# Arduino_CAN_shield_sch_V1_0.net
KiCad netlist of a schematic drawn in Altium Designer
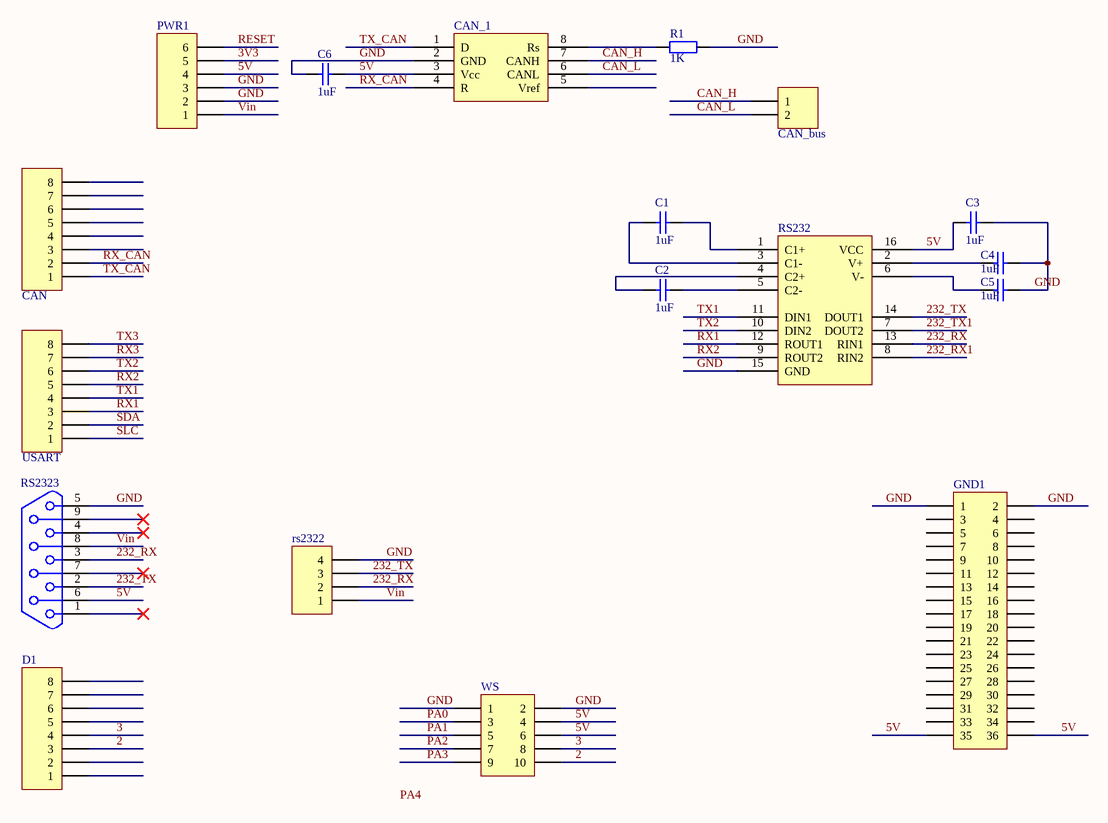
[diagram p0: Arduino CAN shield sch_V1.0.SchDoc]

(export (version "E")
  (design (tool "Eeschema 10.0.6"))
  (components
    (comp (ref "C1")
      (value "1uF")
      (footprint "0805C")
      (description "Capacitor")
      (fields (field (name "PUBLISHER") "Altium Limited"))
      (libsource (lib "Schlib1") (part "Cap"))
    )
    (comp (ref "C2")
      (value "1uF")
      (footprint "0805C")
      (description "Capacitor")
      (fields (field (name "PUBLISHER") "Altium Limited"))
      (libsource (lib "Schlib1") (part "Cap"))
    )
    (comp (ref "C3")
      (value "1uF")
      (footprint "0805C")
      (description "Capacitor")
      (fields (field (name "PUBLISHER") "Altium Limited"))
      (libsource (lib "Schlib1") (part "Cap"))
    )
    (comp (ref "C4")
      (value "1uF")
      (footprint "0805C")
      (description "Capacitor")
      (fields (field (name "PUBLISHER") "Altium Limited"))
      (libsource (lib "Schlib1") (part "Cap"))
    )
    (comp (ref "C5")
      (value "1uF")
      (footprint "0805C")
      (description "Capacitor")
      (fields (field (name "PUBLISHER") "Altium Limited"))
      (libsource (lib "Schlib1") (part "Cap"))
    )
    (comp (ref "C6")
      (value "1uF")
      (footprint "0805C")
      (description "Capacitor")
      (fields (field (name "PUBLISHER") "Altium Limited"))
      (libsource (lib "Schlib1") (part "Cap"))
    )
    (comp (ref "CAN") (value "Header 8") (footprint "HDR1X8") (libsource (lib "Schlib1") (part "Header 8")))
    (comp (ref "CAN_1") (value "VP230") (footprint "SI4435") (libsource (lib "Schlib1") (part "VP230")))
    (comp (ref "CAN_bus")
      (value "Header 2_3")
      (footprint "HDR1X2-can")
      (description "Header, 2-Pin")
      (fields (field (name "PUBLISHER") "Altium Limited"))
      (libsource (lib "Schlib1") (part "Header 2_3"))
    )
    (comp (ref "D1") (value "Header 8") (footprint "HDR1X8") (libsource (lib "Schlib1") (part "Header 8")))
    (comp (ref "GND1")
      (value "Header 18X2H")
      (footprint "HDR2X18")
      (description "Header, 18-Pin, Dual row, Right Angle")
      (fields (field (name "PUBLISHER") "Altium Limited"))
      (libsource (lib "Schlib1") (part "Header 18X2H"))
    )
    (comp (ref "PWR1")
      (value "Header 6_1")
      (footprint "HDR1X6")
      (description "Header, 6-Pin")
      (fields (field (name "PUBLISHER") "Altium Limited"))
      (libsource (lib "Schlib1") (part "Header 6_1"))
    )
    (comp (ref "R1")
      (value "1K")
      (footprint "0805R")
      (description "Resistor")
      (fields (field (name "PUBLISHER") "Altium Limited"))
      (libsource (lib "Schlib1") (part "Res2"))
    )
    (comp (ref "RS232") (value "MAX232D") (footprint "TSSOP-16") (libsource (lib "Schlib1") (part "MAX232D")))
    (comp (ref "rs2322")
      (value "Header 4_1")
      (footprint "HDR1X4")
      (description "Header, 4-Pin")
      (fields (field (name "PUBLISHER") "Altium Limited"))
      (libsource (lib "Schlib1") (part "Header 4_1"))
    )
    (comp (ref "RS2323") (value "DB9") (footprint "DB9RA/F") (libsource (lib "Schlib1") (part "DB9")))
    (comp (ref "USART") (value "Header 8") (footprint "HDR1X8") (libsource (lib "Schlib1") (part "Header 8")))
    (comp (ref "WS")
      (value "Header 5X2_3")
      (footprint "HDR2X5")
      (description "Header, 5-Pin, Dual row")
      (fields (field (name "PUBLISHER") "Altium Limited"))
      (libsource (lib "Schlib1") (part "Header 5X2_3"))
    )
  )
  (nets
    (net (code "1") (name "/2") (class "Default")
      (node (ref "D1") (pin "3") (pinfunction "3_3") (pintype "passive"))
      (node (ref "WS") (pin "10") (pinfunction "10_10") (pintype "passive"))
    )
    (net (code "2") (name "/3") (class "Default")
      (node (ref "D1") (pin "4") (pinfunction "4_4") (pintype "passive"))
      (node (ref "WS") (pin "8") (pinfunction "8_8") (pintype "passive"))
    )
    (net (code "3") (name "/3V3") (class "Default")
      (node (ref "PWR1") (pin "5") (pinfunction "5_5") (pintype "passive"))
    )
    (net (code "4") (name "/5V") (class "Default")
      (node (ref "C3") (pin "1") (pinfunction "1_1") (pintype "passive"))
      (node (ref "C6") (pin "1") (pinfunction "1_1") (pintype "passive"))
      (node (ref "CAN_1") (pin "3") (pinfunction "Vcc_3") (pintype "passive"))
      (node (ref "GND1") (pin "35") (pinfunction "35_35") (pintype "passive"))
      (node (ref "GND1") (pin "36") (pinfunction "36_36") (pintype "passive"))
      (node (ref "PWR1") (pin "4") (pinfunction "4_4") (pintype "passive"))
      (node (ref "RS232") (pin "16") (pinfunction "VCC_16") (pintype "passive"))
      (node (ref "RS2323") (pin "6") (pinfunction "6_6") (pintype "passive"))
      (node (ref "WS") (pin "4") (pinfunction "4_4") (pintype "passive"))
      (node (ref "WS") (pin "6") (pinfunction "6_6") (pintype "passive"))
    )
    (net (code "5") (name "/232_RX") (class "Default")
      (node (ref "RS232") (pin "13") (pinfunction "RIN1_13") (pintype "passive"))
      (node (ref "RS2323") (pin "3") (pinfunction "3_3") (pintype "passive"))
      (node (ref "rs2322") (pin "2") (pinfunction "2_2") (pintype "passive"))
    )
    (net (code "6") (name "/232_RX1") (class "Default")
      (node (ref "RS232") (pin "8") (pinfunction "RIN2_8") (pintype "passive"))
    )
    (net (code "7") (name "/232_TX") (class "Default")
      (node (ref "RS232") (pin "14") (pinfunction "DOUT1_14") (pintype "passive"))
      (node (ref "RS2323") (pin "2") (pinfunction "2_2") (pintype "passive"))
      (node (ref "rs2322") (pin "3") (pinfunction "3_3") (pintype "passive"))
    )
    (net (code "8") (name "/232_TX1") (class "Default")
      (node (ref "RS232") (pin "7") (pinfunction "DOUT2_7") (pintype "passive"))
    )
    (net (code "9") (name "/CAN_H") (class "Default")
      (node (ref "CAN_1") (pin "7") (pinfunction "CANH_7") (pintype "passive"))
      (node (ref "CAN_bus") (pin "1") (pinfunction "1_1") (pintype "passive"))
    )
    (net (code "10") (name "/CAN_L") (class "Default")
      (node (ref "CAN_1") (pin "6") (pinfunction "CANL_6") (pintype "passive"))
      (node (ref "CAN_bus") (pin "2") (pinfunction "2_2") (pintype "passive"))
    )
    (net (code "11") (name "/GND") (class "Default")
      (node (ref "C3") (pin "2") (pinfunction "2_2") (pintype "passive"))
      (node (ref "C4") (pin "1") (pinfunction "1_1") (pintype "passive"))
      (node (ref "C5") (pin "1") (pinfunction "1_1") (pintype "passive"))
      (node (ref "C6") (pin "2") (pinfunction "2_2") (pintype "passive"))
      (node (ref "CAN_1") (pin "2") (pinfunction "GND_2") (pintype "passive"))
      (node (ref "GND1") (pin "1") (pinfunction "1_1") (pintype "passive"))
      (node (ref "GND1") (pin "2") (pinfunction "2_2") (pintype "passive"))
      (node (ref "PWR1") (pin "2") (pinfunction "2_2") (pintype "passive"))
      (node (ref "PWR1") (pin "3") (pinfunction "3_3") (pintype "passive"))
      (node (ref "R1") (pin "2") (pinfunction "2_2") (pintype "passive"))
      (node (ref "RS232") (pin "15") (pinfunction "GND_15") (pintype "passive"))
      (node (ref "RS2323") (pin "5") (pinfunction "5_5") (pintype "passive"))
      (node (ref "WS") (pin "1") (pinfunction "1_1") (pintype "passive"))
      (node (ref "WS") (pin "2") (pinfunction "2_2") (pintype "passive"))
      (node (ref "rs2322") (pin "4") (pinfunction "4_4") (pintype "passive"))
    )
    (net (code "12") (name "/PA0") (class "Default")
      (node (ref "WS") (pin "3") (pinfunction "3_3") (pintype "passive"))
    )
    (net (code "13") (name "/PA1") (class "Default")
      (node (ref "WS") (pin "5") (pinfunction "5_5") (pintype "passive"))
    )
    (net (code "14") (name "/PA2") (class "Default")
      (node (ref "WS") (pin "7") (pinfunction "7_7") (pintype "passive"))
    )
    (net (code "15") (name "/PA3") (class "Default")
      (node (ref "WS") (pin "9") (pinfunction "9_9") (pintype "passive"))
    )
    (net (code "17") (name "/RESET") (class "Default")
      (node (ref "PWR1") (pin "6") (pinfunction "6_6") (pintype "passive"))
    )
    (net (code "18") (name "/RX1") (class "Default")
      (node (ref "RS232") (pin "12") (pinfunction "ROUT1_12") (pintype "passive"))
      (node (ref "USART") (pin "3") (pinfunction "3_3") (pintype "passive"))
    )
    (net (code "19") (name "/RX2") (class "Default")
      (node (ref "RS232") (pin "9") (pinfunction "ROUT2_9") (pintype "passive"))
      (node (ref "USART") (pin "5") (pinfunction "5_5") (pintype "passive"))
    )
    (net (code "20") (name "/RX3") (class "Default")
      (node (ref "USART") (pin "7") (pinfunction "7_7") (pintype "passive"))
    )
    (net (code "21") (name "/RX_CAN") (class "Default")
      (node (ref "CAN") (pin "2") (pinfunction "2_2") (pintype "passive"))
      (node (ref "CAN_1") (pin "4") (pinfunction "R_4") (pintype "passive"))
    )
    (net (code "22") (name "/SDA") (class "Default")
      (node (ref "USART") (pin "2") (pinfunction "2_2") (pintype "passive"))
    )
    (net (code "23") (name "/SLC") (class "Default")
      (node (ref "USART") (pin "1") (pinfunction "1_1") (pintype "passive"))
    )
    (net (code "24") (name "/TX1") (class "Default")
      (node (ref "RS232") (pin "11") (pinfunction "DIN1_11") (pintype "passive"))
      (node (ref "USART") (pin "4") (pinfunction "4_4") (pintype "passive"))
    )
    (net (code "25") (name "/TX2") (class "Default")
      (node (ref "RS232") (pin "10") (pinfunction "DIN2_10") (pintype "passive"))
      (node (ref "USART") (pin "6") (pinfunction "6_6") (pintype "passive"))
    )
    (net (code "26") (name "/TX3") (class "Default")
      (node (ref "USART") (pin "8") (pinfunction "8_8") (pintype "passive"))
    )
    (net (code "27") (name "/TX_CAN") (class "Default")
      (node (ref "CAN") (pin "1") (pinfunction "1_1") (pintype "passive"))
      (node (ref "CAN_1") (pin "1") (pinfunction "D_1") (pintype "passive"))
    )
    (net (code "28") (name "/Vin") (class "Default")
      (node (ref "PWR1") (pin "1") (pinfunction "1_1") (pintype "passive"))
      (node (ref "RS2323") (pin "8") (pinfunction "8_8") (pintype "passive"))
      (node (ref "rs2322") (pin "1") (pinfunction "1_1") (pintype "passive"))
    )
    (net (code "29") (name "Net-(CAN_1-Rs)") (class "Default")
      (node (ref "CAN_1") (pin "8") (pinfunction "Rs_8") (pintype "passive"))
      (node (ref "R1") (pin "1") (pinfunction "1_1") (pintype "passive"))
    )
    (net (code "30") (name "Net-(RS232-C1+)") (class "Default")
      (node (ref "C1") (pin "1") (pinfunction "1_1") (pintype "passive"))
      (node (ref "RS232") (pin "1") (pinfunction "C1+_1") (pintype "passive"))
    )
    (net (code "31") (name "Net-(RS232-C1-)") (class "Default")
      (node (ref "C1") (pin "2") (pinfunction "2_2") (pintype "passive"))
      (node (ref "RS232") (pin "3") (pinfunction "C1-_3") (pintype "passive"))
    )
    (net (code "32") (name "Net-(RS232-C2+)") (class "Default")
      (node (ref "C2") (pin "2") (pinfunction "2_2") (pintype "passive"))
      (node (ref "RS232") (pin "4") (pinfunction "C2+_4") (pintype "passive"))
    )
    (net (code "33") (name "Net-(RS232-C2-)") (class "Default")
      (node (ref "C2") (pin "1") (pinfunction "1_1") (pintype "passive"))
      (node (ref "RS232") (pin "5") (pinfunction "C2-_5") (pintype "passive"))
    )
    (net (code "34") (name "Net-(RS232-V+)") (class "Default")
      (node (ref "C4") (pin "2") (pinfunction "2_2") (pintype "passive"))
      (node (ref "RS232") (pin "2") (pinfunction "V+_2") (pintype "passive"))
    )
    (net (code "35") (name "Net-(RS232-V-)") (class "Default")
      (node (ref "C5") (pin "2") (pinfunction "2_2") (pintype "passive"))
      (node (ref "RS232") (pin "6") (pinfunction "V-_6") (pintype "passive"))
    )
    (net (code "36") (name "unconnected-(CAN-Pad3)") (class "Default")
      (node (ref "CAN") (pin "3") (pinfunction "3_3") (pintype "passive"))
    )
    (net (code "37") (name "unconnected-(CAN-Pad4)") (class "Default")
      (node (ref "CAN") (pin "4") (pinfunction "4_4") (pintype "passive"))
    )
    (net (code "38") (name "unconnected-(CAN-Pad5)") (class "Default")
      (node (ref "CAN") (pin "5") (pinfunction "5_5") (pintype "passive"))
    )
    (net (code "39") (name "unconnected-(CAN-Pad6)") (class "Default")
      (node (ref "CAN") (pin "6") (pinfunction "6_6") (pintype "passive"))
    )
    (net (code "40") (name "unconnected-(CAN-Pad7)") (class "Default")
      (node (ref "CAN") (pin "7") (pinfunction "7_7") (pintype "passive"))
    )
    (net (code "41") (name "unconnected-(CAN-Pad8)") (class "Default")
      (node (ref "CAN") (pin "8") (pinfunction "8_8") (pintype "passive"))
    )
    (net (code "42") (name "unconnected-(CAN_1-Vref-Pad5)") (class "Default")
      (node (ref "CAN_1") (pin "5") (pinfunction "Vref_5") (pintype "passive"))
    )
    (net (code "43") (name "unconnected-(D1-Pad1)") (class "Default")
      (node (ref "D1") (pin "1") (pinfunction "1_1") (pintype "passive"))
    )
    (net (code "44") (name "unconnected-(D1-Pad2)") (class "Default")
      (node (ref "D1") (pin "2") (pinfunction "2_2") (pintype "passive"))
    )
    (net (code "45") (name "unconnected-(D1-Pad5)") (class "Default")
      (node (ref "D1") (pin "5") (pinfunction "5_5") (pintype "passive"))
    )
    (net (code "46") (name "unconnected-(D1-Pad6)") (class "Default")
      (node (ref "D1") (pin "6") (pinfunction "6_6") (pintype "passive"))
    )
    (net (code "47") (name "unconnected-(D1-Pad7)") (class "Default")
      (node (ref "D1") (pin "7") (pinfunction "7_7") (pintype "passive"))
    )
    (net (code "48") (name "unconnected-(D1-Pad8)") (class "Default")
      (node (ref "D1") (pin "8") (pinfunction "8_8") (pintype "passive"))
    )
    (net (code "49") (name "unconnected-(GND1-Pad3)") (class "Default")
      (node (ref "GND1") (pin "3") (pinfunction "3_3") (pintype "passive"))
    )
    (net (code "50") (name "unconnected-(GND1-Pad4)") (class "Default")
      (node (ref "GND1") (pin "4") (pinfunction "4_4") (pintype "passive"))
    )
    (net (code "51") (name "unconnected-(GND1-Pad5)") (class "Default")
      (node (ref "GND1") (pin "5") (pinfunction "5_5") (pintype "passive"))
    )
    (net (code "52") (name "unconnected-(GND1-Pad6)") (class "Default")
      (node (ref "GND1") (pin "6") (pinfunction "6_6") (pintype "passive"))
    )
    (net (code "53") (name "unconnected-(GND1-Pad7)") (class "Default")
      (node (ref "GND1") (pin "7") (pinfunction "7_7") (pintype "passive"))
    )
    (net (code "54") (name "unconnected-(GND1-Pad8)") (class "Default")
      (node (ref "GND1") (pin "8") (pinfunction "8_8") (pintype "passive"))
    )
    (net (code "55") (name "unconnected-(GND1-Pad9)") (class "Default")
      (node (ref "GND1") (pin "9") (pinfunction "9_9") (pintype "passive"))
    )
    (net (code "56") (name "unconnected-(GND1-Pad10)") (class "Default")
      (node (ref "GND1") (pin "10") (pinfunction "10_10") (pintype "passive"))
    )
    (net (code "57") (name "unconnected-(GND1-Pad11)") (class "Default")
      (node (ref "GND1") (pin "11") (pinfunction "11_11") (pintype "passive"))
    )
    (net (code "58") (name "unconnected-(GND1-Pad12)") (class "Default")
      (node (ref "GND1") (pin "12") (pinfunction "12_12") (pintype "passive"))
    )
    (net (code "59") (name "unconnected-(GND1-Pad13)") (class "Default")
      (node (ref "GND1") (pin "13") (pinfunction "13_13") (pintype "passive"))
    )
    (net (code "60") (name "unconnected-(GND1-Pad14)") (class "Default")
      (node (ref "GND1") (pin "14") (pinfunction "14_14") (pintype "passive"))
    )
    (net (code "61") (name "unconnected-(GND1-Pad15)") (class "Default")
      (node (ref "GND1") (pin "15") (pinfunction "15_15") (pintype "passive"))
    )
    (net (code "62") (name "unconnected-(GND1-Pad16)") (class "Default")
      (node (ref "GND1") (pin "16") (pinfunction "16_16") (pintype "passive"))
    )
    (net (code "63") (name "unconnected-(GND1-Pad17)") (class "Default")
      (node (ref "GND1") (pin "17") (pinfunction "17_17") (pintype "passive"))
    )
    (net (code "64") (name "unconnected-(GND1-Pad18)") (class "Default")
      (node (ref "GND1") (pin "18") (pinfunction "18_18") (pintype "passive"))
    )
    (net (code "65") (name "unconnected-(GND1-Pad19)") (class "Default")
      (node (ref "GND1") (pin "19") (pinfunction "19_19") (pintype "passive"))
    )
    (net (code "66") (name "unconnected-(GND1-Pad20)") (class "Default")
      (node (ref "GND1") (pin "20") (pinfunction "20_20") (pintype "passive"))
    )
    (net (code "67") (name "unconnected-(GND1-Pad21)") (class "Default")
      (node (ref "GND1") (pin "21") (pinfunction "21_21") (pintype "passive"))
    )
    (net (code "68") (name "unconnected-(GND1-Pad22)") (class "Default")
      (node (ref "GND1") (pin "22") (pinfunction "22_22") (pintype "passive"))
    )
    (net (code "69") (name "unconnected-(GND1-Pad23)") (class "Default")
      (node (ref "GND1") (pin "23") (pinfunction "23_23") (pintype "passive"))
    )
    (net (code "70") (name "unconnected-(GND1-Pad24)") (class "Default")
      (node (ref "GND1") (pin "24") (pinfunction "24_24") (pintype "passive"))
    )
    (net (code "71") (name "unconnected-(GND1-Pad25)") (class "Default")
      (node (ref "GND1") (pin "25") (pinfunction "25_25") (pintype "passive"))
    )
    (net (code "72") (name "unconnected-(GND1-Pad26)") (class "Default")
      (node (ref "GND1") (pin "26") (pinfunction "26_26") (pintype "passive"))
    )
    (net (code "73") (name "unconnected-(GND1-Pad27)") (class "Default")
      (node (ref "GND1") (pin "27") (pinfunction "27_27") (pintype "passive"))
    )
    (net (code "74") (name "unconnected-(GND1-Pad28)") (class "Default")
      (node (ref "GND1") (pin "28") (pinfunction "28_28") (pintype "passive"))
    )
    (net (code "75") (name "unconnected-(GND1-Pad29)") (class "Default")
      (node (ref "GND1") (pin "29") (pinfunction "29_29") (pintype "passive"))
    )
    (net (code "76") (name "unconnected-(GND1-Pad30)") (class "Default")
      (node (ref "GND1") (pin "30") (pinfunction "30_30") (pintype "passive"))
    )
    (net (code "77") (name "unconnected-(GND1-Pad31)") (class "Default")
      (node (ref "GND1") (pin "31") (pinfunction "31_31") (pintype "passive"))
    )
    (net (code "78") (name "unconnected-(GND1-Pad32)") (class "Default")
      (node (ref "GND1") (pin "32") (pinfunction "32_32") (pintype "passive"))
    )
    (net (code "79") (name "unconnected-(GND1-Pad33)") (class "Default")
      (node (ref "GND1") (pin "33") (pinfunction "33_33") (pintype "passive"))
    )
    (net (code "80") (name "unconnected-(GND1-Pad34)") (class "Default")
      (node (ref "GND1") (pin "34") (pinfunction "34_34") (pintype "passive"))
    )
    (net (code "81") (name "unconnected-(RS2323-Pad1)") (class "Default")
      (node (ref "RS2323") (pin "1") (pinfunction "1_1") (pintype "passive+no_connect"))
    )
    (net (code "82") (name "unconnected-(RS2323-Pad4)") (class "Default")
      (node (ref "RS2323") (pin "4") (pinfunction "4_4") (pintype "passive+no_connect"))
    )
    (net (code "83") (name "unconnected-(RS2323-Pad7)") (class "Default")
      (node (ref "RS2323") (pin "7") (pinfunction "7_7") (pintype "passive+no_connect"))
    )
    (net (code "84") (name "unconnected-(RS2323-Pad9)") (class "Default")
      (node (ref "RS2323") (pin "9") (pinfunction "9_9") (pintype "passive+no_connect"))
    )
  )
)
